# ULN2803_MOSFETS.net
KiCad netlist of a schematic drawn in Altium Designer
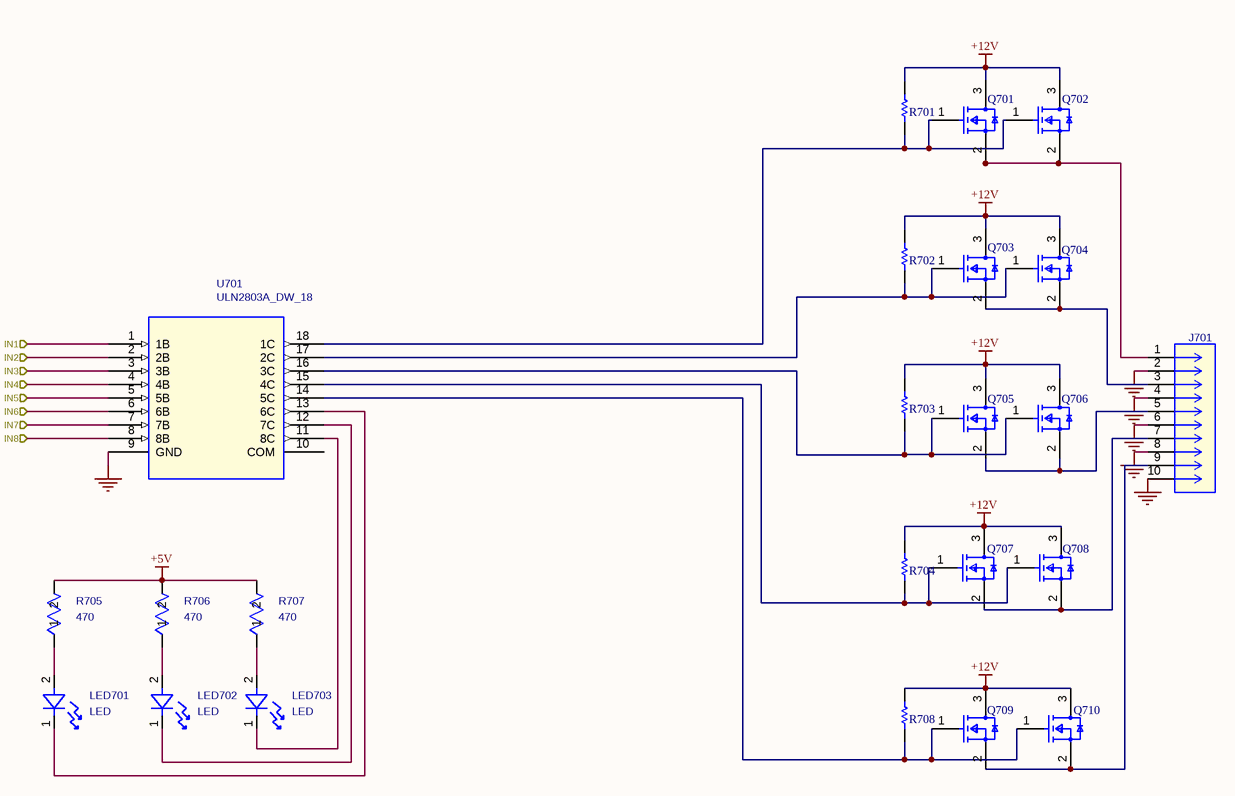
[diagram p0: ULN2803+MOSFETS.SchDoc]

(export (version "E")
  (design (tool "Eeschema 10.0.6"))
  (components
    (comp (ref "J701")
      (value "CONN_1924389")
      (footprint "TerminalBlock_Phoenix_MKDS-3-10-5.08_1x10_P5.08mm_Horizontal")
      (fields
        (field (name "MANUFACTURER_PART_NUMBER") "1924389")
        (field (name "COPYRIGHT") "Copyright (C) 2025 Ultra Librarian. All rights reserved.")
      )
      (libsource (lib "*") (part "1924389"))
    )
    (comp (ref "LED701")
      (value "LED")
      (footprint "LED_0805_2012Metric_Pad1.15x1.40mm_HandSolder")
      (description "https://sharvielectronics.com/product/yellow-led-17-21uyc-s530-a2-tr8-0805-package/")
      (fields
        (field (name "MANUFACTURER_PART_NUMBER") "QTLP600C3TR")
        (field (name "COPYRIGHT") "Copyright (C) 2025 Ultra Librarian. All rights reserved.")
      )
      (libsource (lib "*") (part "QTLP600C3TR"))
    )
    (comp (ref "LED702")
      (value "LED")
      (footprint "LED_0805_2012Metric_Pad1.15x1.40mm_HandSolder")
      (description "https://sharvielectronics.com/product/yellow-led-17-21uyc-s530-a2-tr8-0805-package/")
      (fields
        (field (name "MANUFACTURER_PART_NUMBER") "QTLP600C3TR")
        (field (name "COPYRIGHT") "Copyright (C) 2025 Ultra Librarian. All rights reserved.")
      )
      (libsource (lib "*") (part "QTLP600C3TR"))
    )
    (comp (ref "LED703")
      (value "LED")
      (footprint "LED_0805_2012Metric_Pad1.15x1.40mm_HandSolder")
      (description "https://sharvielectronics.com/product/yellow-led-17-21uyc-s530-a2-tr8-0805-package/")
      (fields
        (field (name "MANUFACTURER_PART_NUMBER") "QTLP600C3TR")
        (field (name "COPYRIGHT") "Copyright (C) 2025 Ultra Librarian. All rights reserved.")
      )
      (libsource (lib "*") (part "QTLP600C3TR"))
    )
    (comp (ref "Q701")
      (value "3b9c635fedb024a5347a57b145af9cc")
      (footprint "FP-S-03946-IPC_C")
      (description "MOSFET N-CH 100V 1.15A SOT23-3")
      (fields
        (field (name "MANUFACTURER PART NUMBER") "SI2328DS-T1-E3")
        (field (name "OCTOPART") "https://octopart.com/si2328ds-t1-e3-vishay-40951139")
      )
      (libsource (lib "Altium Content Vault") (part "3b9c635fedb024a5347a57b145af9cc"))
    )
    (comp (ref "Q702")
      (value "3b9c635fedb024a5347a57b145af9cc")
      (footprint "FP-S-03946-IPC_C")
      (description "MOSFET N-CH 100V 1.15A SOT23-3")
      (fields
        (field (name "MANUFACTURER PART NUMBER") "SI2328DS-T1-E3")
        (field (name "OCTOPART") "https://octopart.com/si2328ds-t1-e3-vishay-40951139")
      )
      (libsource (lib "Altium Content Vault") (part "3b9c635fedb024a5347a57b145af9cc"))
    )
    (comp (ref "Q703")
      (value "3b9c635fedb024a5347a57b145af9cc")
      (footprint "FP-S-03946-IPC_C")
      (description "MOSFET N-CH 100V 1.15A SOT23-3")
      (fields
        (field (name "MANUFACTURER PART NUMBER") "SI2328DS-T1-E3")
        (field (name "OCTOPART") "https://octopart.com/si2328ds-t1-e3-vishay-40951139")
      )
      (libsource (lib "Altium Content Vault") (part "3b9c635fedb024a5347a57b145af9cc"))
    )
    (comp (ref "Q704")
      (value "3b9c635fedb024a5347a57b145af9cc")
      (footprint "FP-S-03946-IPC_C")
      (description "MOSFET N-CH 100V 1.15A SOT23-3")
      (fields
        (field (name "MANUFACTURER PART NUMBER") "SI2328DS-T1-E3")
        (field (name "OCTOPART") "https://octopart.com/si2328ds-t1-e3-vishay-40951139")
      )
      (libsource (lib "Altium Content Vault") (part "3b9c635fedb024a5347a57b145af9cc"))
    )
    (comp (ref "Q705")
      (value "3b9c635fedb024a5347a57b145af9cc")
      (footprint "FP-S-03946-IPC_C")
      (description "MOSFET N-CH 100V 1.15A SOT23-3")
      (fields
        (field (name "MANUFACTURER PART NUMBER") "SI2328DS-T1-E3")
        (field (name "OCTOPART") "https://octopart.com/si2328ds-t1-e3-vishay-40951139")
      )
      (libsource (lib "Altium Content Vault") (part "3b9c635fedb024a5347a57b145af9cc"))
    )
    (comp (ref "Q706")
      (value "3b9c635fedb024a5347a57b145af9cc")
      (footprint "FP-S-03946-IPC_C")
      (description "MOSFET N-CH 100V 1.15A SOT23-3")
      (fields
        (field (name "MANUFACTURER PART NUMBER") "SI2328DS-T1-E3")
        (field (name "OCTOPART") "https://octopart.com/si2328ds-t1-e3-vishay-40951139")
      )
      (libsource (lib "Altium Content Vault") (part "3b9c635fedb024a5347a57b145af9cc"))
    )
    (comp (ref "Q707")
      (value "3b9c635fedb024a5347a57b145af9cc")
      (footprint "FP-S-03946-IPC_C")
      (description "MOSFET N-CH 100V 1.15A SOT23-3")
      (fields
        (field (name "MANUFACTURER PART NUMBER") "SI2328DS-T1-E3")
        (field (name "OCTOPART") "https://octopart.com/si2328ds-t1-e3-vishay-40951139")
      )
      (libsource (lib "Altium Content Vault") (part "3b9c635fedb024a5347a57b145af9cc"))
    )
    (comp (ref "Q708")
      (value "3b9c635fedb024a5347a57b145af9cc")
      (footprint "FP-S-03946-IPC_C")
      (description "MOSFET N-CH 100V 1.15A SOT23-3")
      (fields
        (field (name "MANUFACTURER PART NUMBER") "SI2328DS-T1-E3")
        (field (name "OCTOPART") "https://octopart.com/si2328ds-t1-e3-vishay-40951139")
      )
      (libsource (lib "Altium Content Vault") (part "3b9c635fedb024a5347a57b145af9cc"))
    )
    (comp (ref "Q709")
      (value "3b9c635fedb024a5347a57b145af9cc")
      (footprint "FP-S-03946-IPC_C")
      (description "MOSFET N-CH 100V 1.15A SOT23-3")
      (fields
        (field (name "MANUFACTURER PART NUMBER") "SI2328DS-T1-E3")
        (field (name "OCTOPART") "https://octopart.com/si2328ds-t1-e3-vishay-40951139")
      )
      (libsource (lib "Altium Content Vault") (part "3b9c635fedb024a5347a57b145af9cc"))
    )
    (comp (ref "Q710")
      (value "3b9c635fedb024a5347a57b145af9cc")
      (footprint "FP-S-03946-IPC_C")
      (description "MOSFET N-CH 100V 1.15A SOT23-3")
      (fields
        (field (name "MANUFACTURER PART NUMBER") "SI2328DS-T1-E3")
        (field (name "OCTOPART") "https://octopart.com/si2328ds-t1-e3-vishay-40951139")
      )
      (libsource (lib "Altium Content Vault") (part "3b9c635fedb024a5347a57b145af9cc"))
    )
    (comp (ref "R701")
      (value "RC0603FR-075K6L")
      (footprint "RESC1608X55X25NL10T15")
      (description "Chip Resistor, 5.6 KOhm, +/- 1%, 0.1 W, -55 to 155 degC, 0603 (1608 Metric), RoHS, Tape and Reel")
      (fields (field (name "TOLERANCE") "1%"))
      (libsource (lib "Altium Content Vault") (part "RES-2"))
    )
    (comp (ref "R702")
      (value "RC0603FR-075K6L")
      (footprint "RESC1608X55X25NL10T15")
      (description "Chip Resistor, 5.6 KOhm, +/- 1%, 0.1 W, -55 to 155 degC, 0603 (1608 Metric), RoHS, Tape and Reel")
      (fields (field (name "TOLERANCE") "1%"))
      (libsource (lib "Altium Content Vault") (part "RES-2"))
    )
    (comp (ref "R703")
      (value "RC0603FR-075K6L")
      (footprint "RESC1608X55X25NL10T15")
      (description "Chip Resistor, 5.6 KOhm, +/- 1%, 0.1 W, -55 to 155 degC, 0603 (1608 Metric), RoHS, Tape and Reel")
      (fields (field (name "TOLERANCE") "1%"))
      (libsource (lib "Altium Content Vault") (part "RES-2"))
    )
    (comp (ref "R704")
      (value "RC0603FR-075K6L")
      (footprint "RESC1608X55X25NL10T15")
      (description "Chip Resistor, 5.6 KOhm, +/- 1%, 0.1 W, -55 to 155 degC, 0603 (1608 Metric), RoHS, Tape and Reel")
      (fields (field (name "TOLERANCE") "1%"))
      (libsource (lib "Altium Content Vault") (part "RES-2"))
    )
    (comp (ref "R705")
      (value "470")
      (footprint "R_0603_1608Metric_Pad0.98x0.95mm_HandSolder")
      (fields
        (field (name "MANUFACTURER_PART_NUMBER") "RCT02470RF")
        (field (name "COPYRIGHT") "Copyright (C) 2025 Ultra Librarian. All rights reserved.")
      )
      (libsource (lib "*") (part "CRGCQ0402F100K"))
    )
    (comp (ref "R706")
      (value "470")
      (footprint "R_0603_1608Metric_Pad0.98x0.95mm_HandSolder")
      (fields
        (field (name "MANUFACTURER_PART_NUMBER") "RCT02470RF")
        (field (name "COPYRIGHT") "Copyright (C) 2025 Ultra Librarian. All rights reserved.")
      )
      (libsource (lib "*") (part "CRGCQ0402F100K"))
    )
    (comp (ref "R707")
      (value "470")
      (footprint "R_0603_1608Metric_Pad0.98x0.95mm_HandSolder")
      (fields
        (field (name "MANUFACTURER_PART_NUMBER") "RCT02470RF")
        (field (name "COPYRIGHT") "Copyright (C) 2025 Ultra Librarian. All rights reserved.")
      )
      (libsource (lib "*") (part "CRGCQ0402F100K"))
    )
    (comp (ref "R708")
      (value "RC0603FR-075K6L")
      (footprint "RESC1608X55X25NL10T15")
      (description "Chip Resistor, 5.6 KOhm, +/- 1%, 0.1 W, -55 to 155 degC, 0603 (1608 Metric), RoHS, Tape and Reel")
      (fields (field (name "TOLERANCE") "1%"))
      (libsource (lib "Altium Content Vault") (part "RES-2"))
    )
    (comp (ref "U701")
      (value "ULN2803A_DW_18")
      (footprint "DW18")
      (fields
        (field (name "MANUFACTURER_PART_NUMBER") "ULN2803ADW")
        (field (name "COPYRIGHT") "Copyright (C) 2025 Ultra Librarian. All rights reserved.")
      )
      (libsource (lib "*") (part "ULN2803ADW"))
    )
  )
  (nets
    (net (code "1") (name "+5V") (class "Default")
      (node (ref "R705") (pin "2") (pinfunction "2_2") (pintype "passive"))
      (node (ref "R706") (pin "2") (pinfunction "2_2") (pintype "passive"))
      (node (ref "R707") (pin "2") (pinfunction "2_2") (pintype "passive"))
    )
    (net (code "2") (name "+12V") (class "Default")
      (node (ref "Q701") (pin "3") (pinfunction "D_3") (pintype "passive"))
      (node (ref "Q702") (pin "3") (pinfunction "D_3") (pintype "passive"))
      (node (ref "Q703") (pin "3") (pinfunction "D_3") (pintype "passive"))
      (node (ref "Q704") (pin "3") (pinfunction "D_3") (pintype "passive"))
      (node (ref "Q705") (pin "3") (pinfunction "D_3") (pintype "passive"))
      (node (ref "Q706") (pin "3") (pinfunction "D_3") (pintype "passive"))
      (node (ref "Q707") (pin "3") (pinfunction "D_3") (pintype "passive"))
      (node (ref "Q708") (pin "3") (pinfunction "D_3") (pintype "passive"))
      (node (ref "Q709") (pin "3") (pinfunction "D_3") (pintype "passive"))
      (node (ref "Q710") (pin "3") (pinfunction "D_3") (pintype "passive"))
      (node (ref "R701") (pin "2") (pinfunction "2_2") (pintype "passive"))
      (node (ref "R702") (pin "2") (pinfunction "2_2") (pintype "passive"))
      (node (ref "R703") (pin "2") (pinfunction "2_2") (pintype "passive"))
      (node (ref "R704") (pin "2") (pinfunction "2_2") (pintype "passive"))
      (node (ref "R708") (pin "2") (pinfunction "2_2") (pintype "passive"))
    )
    (net (code "3") (name "/IN1") (class "Default")
      (node (ref "U701") (pin "1") (pinfunction "1B_1") (pintype "input"))
    )
    (net (code "4") (name "/IN2") (class "Default")
      (node (ref "U701") (pin "2") (pinfunction "2B_2") (pintype "input"))
    )
    (net (code "5") (name "/IN3") (class "Default")
      (node (ref "U701") (pin "3") (pinfunction "3B_3") (pintype "input"))
    )
    (net (code "6") (name "/IN4") (class "Default")
      (node (ref "U701") (pin "4") (pinfunction "4B_4") (pintype "input"))
    )
    (net (code "7") (name "/IN5") (class "Default")
      (node (ref "U701") (pin "5") (pinfunction "5B_5") (pintype "input"))
    )
    (net (code "8") (name "/IN6") (class "Default")
      (node (ref "U701") (pin "6") (pinfunction "6B_6") (pintype "input"))
    )
    (net (code "9") (name "/IN7") (class "Default")
      (node (ref "U701") (pin "7") (pinfunction "7B_7") (pintype "input"))
    )
    (net (code "10") (name "/IN8") (class "Default")
      (node (ref "U701") (pin "8") (pinfunction "8B_8") (pintype "input"))
    )
    (net (code "11") (name "GNDD") (class "Default")
      (node (ref "J701") (pin "10") (pinfunction "10_10") (pintype "passive"))
      (node (ref "J701") (pin "2") (pinfunction "2_2") (pintype "passive"))
      (node (ref "J701") (pin "4") (pinfunction "4_4") (pintype "passive"))
      (node (ref "J701") (pin "6") (pinfunction "6_6") (pintype "passive"))
      (node (ref "J701") (pin "8") (pinfunction "8_8") (pintype "passive"))
      (node (ref "U701") (pin "9") (pinfunction "GND_9") (pintype "power_in"))
    )
    (net (code "12") (name "Net-(LED701-Pad2)") (class "Default")
      (node (ref "LED701") (pin "2") (pinfunction "2_2") (pintype "passive"))
      (node (ref "R705") (pin "1") (pinfunction "1_1") (pintype "passive"))
    )
    (net (code "13") (name "Net-(LED702-Pad2)") (class "Default")
      (node (ref "LED702") (pin "2") (pinfunction "2_2") (pintype "passive"))
      (node (ref "R706") (pin "1") (pinfunction "1_1") (pintype "passive"))
    )
    (net (code "14") (name "Net-(LED703-Pad2)") (class "Default")
      (node (ref "LED703") (pin "2") (pinfunction "2_2") (pintype "passive"))
      (node (ref "R707") (pin "1") (pinfunction "1_1") (pintype "passive"))
    )
    (net (code "15") (name "Net-(Q701-G)") (class "Default")
      (node (ref "Q701") (pin "1") (pinfunction "G_1") (pintype "passive"))
      (node (ref "Q702") (pin "1") (pinfunction "G_1") (pintype "passive"))
      (node (ref "R701") (pin "1") (pinfunction "1_1") (pintype "passive"))
      (node (ref "U701") (pin "18") (pinfunction "1C_18") (pintype "output"))
    )
    (net (code "16") (name "Net-(Q701-S)") (class "Default")
      (node (ref "J701") (pin "1") (pinfunction "1_1") (pintype "passive"))
      (node (ref "Q701") (pin "2") (pinfunction "S_2") (pintype "passive"))
      (node (ref "Q702") (pin "2") (pinfunction "S_2") (pintype "passive"))
    )
    (net (code "17") (name "Net-(Q703-G)") (class "Default")
      (node (ref "Q703") (pin "1") (pinfunction "G_1") (pintype "passive"))
      (node (ref "Q704") (pin "1") (pinfunction "G_1") (pintype "passive"))
      (node (ref "R702") (pin "1") (pinfunction "1_1") (pintype "passive"))
      (node (ref "U701") (pin "17") (pinfunction "2C_17") (pintype "output"))
    )
    (net (code "18") (name "Net-(Q703-S)") (class "Default")
      (node (ref "J701") (pin "3") (pinfunction "3_3") (pintype "passive"))
      (node (ref "Q703") (pin "2") (pinfunction "S_2") (pintype "passive"))
      (node (ref "Q704") (pin "2") (pinfunction "S_2") (pintype "passive"))
    )
    (net (code "19") (name "Net-(Q705-G)") (class "Default")
      (node (ref "Q705") (pin "1") (pinfunction "G_1") (pintype "passive"))
      (node (ref "Q706") (pin "1") (pinfunction "G_1") (pintype "passive"))
      (node (ref "R703") (pin "1") (pinfunction "1_1") (pintype "passive"))
      (node (ref "U701") (pin "16") (pinfunction "3C_16") (pintype "output"))
    )
    (net (code "20") (name "Net-(Q705-S)") (class "Default")
      (node (ref "J701") (pin "5") (pinfunction "5_5") (pintype "passive"))
      (node (ref "Q705") (pin "2") (pinfunction "S_2") (pintype "passive"))
      (node (ref "Q706") (pin "2") (pinfunction "S_2") (pintype "passive"))
    )
    (net (code "21") (name "Net-(Q707-G)") (class "Default")
      (node (ref "Q707") (pin "1") (pinfunction "G_1") (pintype "passive"))
      (node (ref "Q708") (pin "1") (pinfunction "G_1") (pintype "passive"))
      (node (ref "R704") (pin "1") (pinfunction "1_1") (pintype "passive"))
      (node (ref "U701") (pin "15") (pinfunction "4C_15") (pintype "output"))
    )
    (net (code "22") (name "Net-(Q707-S)") (class "Default")
      (node (ref "J701") (pin "7") (pinfunction "7_7") (pintype "passive"))
      (node (ref "Q707") (pin "2") (pinfunction "S_2") (pintype "passive"))
      (node (ref "Q708") (pin "2") (pinfunction "S_2") (pintype "passive"))
    )
    (net (code "23") (name "Net-(Q709-G)") (class "Default")
      (node (ref "Q709") (pin "1") (pinfunction "G_1") (pintype "passive"))
      (node (ref "Q710") (pin "1") (pinfunction "G_1") (pintype "passive"))
      (node (ref "R708") (pin "1") (pinfunction "1_1") (pintype "passive"))
      (node (ref "U701") (pin "14") (pinfunction "5C_14") (pintype "output"))
    )
    (net (code "24") (name "Net-(Q709-S)") (class "Default")
      (node (ref "J701") (pin "9") (pinfunction "9_9") (pintype "passive"))
      (node (ref "Q709") (pin "2") (pinfunction "S_2") (pintype "passive"))
      (node (ref "Q710") (pin "2") (pinfunction "S_2") (pintype "passive"))
    )
    (net (code "25") (name "Net-(U701-6C)") (class "Default")
      (node (ref "LED701") (pin "1") (pinfunction "1_1") (pintype "passive"))
      (node (ref "U701") (pin "13") (pinfunction "6C_13") (pintype "output"))
    )
    (net (code "26") (name "Net-(U701-7C)") (class "Default")
      (node (ref "LED702") (pin "1") (pinfunction "1_1") (pintype "passive"))
      (node (ref "U701") (pin "12") (pinfunction "7C_12") (pintype "output"))
    )
    (net (code "27") (name "Net-(U701-8C)") (class "Default")
      (node (ref "LED703") (pin "1") (pinfunction "1_1") (pintype "passive"))
      (node (ref "U701") (pin "11") (pinfunction "8C_11") (pintype "output"))
    )
    (net (code "28") (name "unconnected-(U701-COM-Pad10)") (class "Default")
      (node (ref "U701") (pin "10") (pinfunction "COM_10") (pintype "passive"))
    )
  )
)
